# MAME-Controller.net
KiCad netlist of a schematic drawn in EAGLE
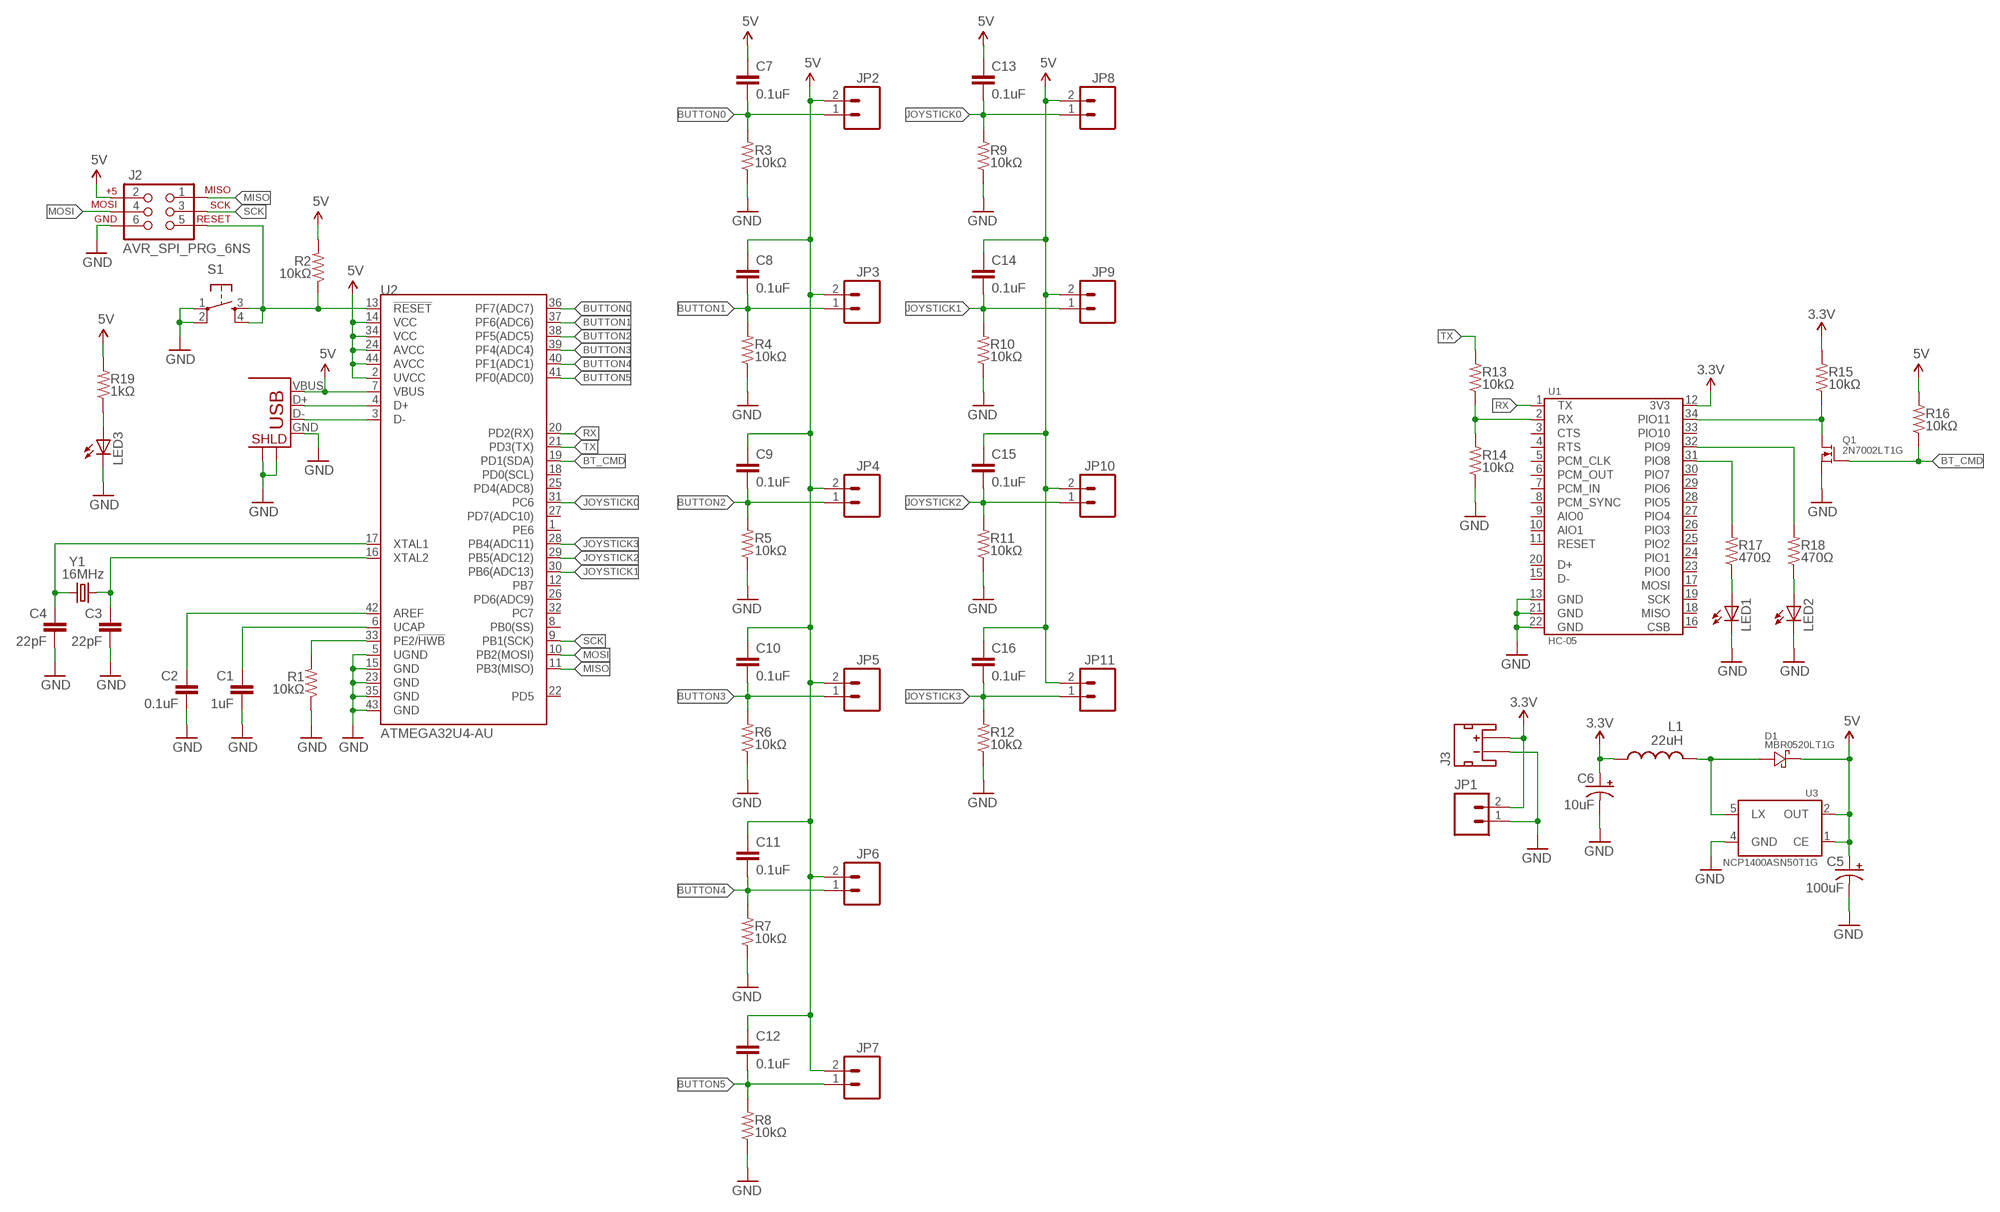
[diagram p0: schematic, sheet 1]

(export (version "E")
  (design (tool "Eeschema 10.0.6"))
  (components
    (comp (ref "C1")
      (value "1uF")
      (footprint "eagle-import:0805")
      (libsource (lib "eagle-import") (part "CAP0805"))
    )
    (comp (ref "C2")
      (value "0.1uF")
      (footprint "eagle-import:0805")
      (libsource (lib "eagle-import") (part "CAP0805"))
    )
    (comp (ref "C3")
      (value "22pF")
      (footprint "eagle-import:0805")
      (libsource (lib "eagle-import") (part "CAP0805"))
    )
    (comp (ref "C4")
      (value "22pF")
      (footprint "eagle-import:0805")
      (libsource (lib "eagle-import") (part "CAP0805"))
    )
    (comp (ref "C5")
      (value "100uF")
      (footprint "eagle-import:CAP_POL-0.35X0.5")
      (libsource (lib "eagle-import") (part "CAP_POL-0.35X0.5"))
    )
    (comp (ref "C6")
      (value "10uF")
      (footprint "eagle-import:EIA3216-KIT")
      (libsource (lib "eagle-import") (part "CAP_POL1206-KIT"))
    )
    (comp (ref "C7")
      (value "0.1uF")
      (footprint "eagle-import:0805")
      (libsource (lib "eagle-import") (part "CAP0805"))
    )
    (comp (ref "C8")
      (value "0.1uF")
      (footprint "eagle-import:0805")
      (libsource (lib "eagle-import") (part "CAP0805"))
    )
    (comp (ref "C9")
      (value "0.1uF")
      (footprint "eagle-import:0805")
      (libsource (lib "eagle-import") (part "CAP0805"))
    )
    (comp (ref "C10")
      (value "0.1uF")
      (footprint "eagle-import:0805")
      (libsource (lib "eagle-import") (part "CAP0805"))
    )
    (comp (ref "C11")
      (value "0.1uF")
      (footprint "eagle-import:0805")
      (libsource (lib "eagle-import") (part "CAP0805"))
    )
    (comp (ref "C12")
      (value "0.1uF")
      (footprint "eagle-import:0805")
      (libsource (lib "eagle-import") (part "CAP0805"))
    )
    (comp (ref "C13")
      (value "0.1uF")
      (footprint "eagle-import:0805")
      (libsource (lib "eagle-import") (part "CAP0805"))
    )
    (comp (ref "C14")
      (value "0.1uF")
      (footprint "eagle-import:0805")
      (libsource (lib "eagle-import") (part "CAP0805"))
    )
    (comp (ref "C15")
      (value "0.1uF")
      (footprint "eagle-import:0805")
      (libsource (lib "eagle-import") (part "CAP0805"))
    )
    (comp (ref "C16")
      (value "0.1uF")
      (footprint "eagle-import:0805")
      (libsource (lib "eagle-import") (part "CAP0805"))
    )
    (comp (ref "D1")
      (value "MBR0520LT1G")
      (footprint "eagle-import:SOD123")
      (libsource (lib "eagle-import") (part "MBR0520LT1G"))
    )
    (comp (ref "J1")
      (value "USB+SHIELD")
      (footprint "eagle-import:USB-B-PTH")
      (libsource (lib "eagle-import") (part "USB+SHIELD"))
    )
    (comp (ref "J2")
      (value "AVR_SPI_PRG_6NS")
      (footprint "eagle-import:2X3-NS")
      (libsource (lib "eagle-import") (part "AVR_SPI_PRG_6NS"))
    )
    (comp (ref "J3")
      (value "JST_2MM_MALE")
      (footprint "eagle-import:JST-2-SMD")
      (libsource (lib "eagle-import") (part "JST_2MM_MALE"))
    )
    (comp (ref "JP1")
      (value "M02PTH")
      (footprint "eagle-import:1X02")
      (libsource (lib "eagle-import") (part "M02PTH"))
    )
    (comp (ref "JP2")
      (value "M02POLAR")
      (footprint "eagle-import:MOLEX-1X2")
      (libsource (lib "eagle-import") (part "M02POLAR"))
    )
    (comp (ref "JP3")
      (value "M02POLAR")
      (footprint "eagle-import:MOLEX-1X2")
      (libsource (lib "eagle-import") (part "M02POLAR"))
    )
    (comp (ref "JP4")
      (value "M02POLAR")
      (footprint "eagle-import:MOLEX-1X2")
      (libsource (lib "eagle-import") (part "M02POLAR"))
    )
    (comp (ref "JP5")
      (value "M02POLAR")
      (footprint "eagle-import:MOLEX-1X2")
      (libsource (lib "eagle-import") (part "M02POLAR"))
    )
    (comp (ref "JP6")
      (value "M02POLAR")
      (footprint "eagle-import:MOLEX-1X2")
      (libsource (lib "eagle-import") (part "M02POLAR"))
    )
    (comp (ref "JP7")
      (value "M02POLAR")
      (footprint "eagle-import:MOLEX-1X2")
      (libsource (lib "eagle-import") (part "M02POLAR"))
    )
    (comp (ref "JP8")
      (value "M02POLAR")
      (footprint "eagle-import:MOLEX-1X2")
      (libsource (lib "eagle-import") (part "M02POLAR"))
    )
    (comp (ref "JP9")
      (value "M02POLAR")
      (footprint "eagle-import:MOLEX-1X2")
      (libsource (lib "eagle-import") (part "M02POLAR"))
    )
    (comp (ref "JP10")
      (value "M02POLAR")
      (footprint "eagle-import:MOLEX-1X2")
      (libsource (lib "eagle-import") (part "M02POLAR"))
    )
    (comp (ref "JP11")
      (value "M02POLAR")
      (footprint "eagle-import:MOLEX-1X2")
      (libsource (lib "eagle-import") (part "M02POLAR"))
    )
    (comp (ref "L1")
      (value "22uH")
      (footprint "eagle-import:0805")
      (libsource (lib "eagle-import") (part "INDUCTOR0805"))
    )
    (comp (ref "LED1")
      (value "LED-FKIT-1206")
      (footprint "eagle-import:FKIT-LED-1206")
      (libsource (lib "eagle-import") (part "LED-FKIT-1206"))
    )
    (comp (ref "LED2")
      (value "LED-FKIT-1206")
      (footprint "eagle-import:FKIT-LED-1206")
      (libsource (lib "eagle-import") (part "LED-FKIT-1206"))
    )
    (comp (ref "LED3")
      (value "LED-FKIT-1206")
      (footprint "eagle-import:FKIT-LED-1206")
      (libsource (lib "eagle-import") (part "LED-FKIT-1206"))
    )
    (comp (ref "Q1")
      (value "2N7002LT1G")
      (footprint "eagle-import:SOT23")
      (libsource (lib "eagle-import") (part "2N7002LT1G"))
    )
    (comp (ref "R1")
      (value "10kΩ")
      (footprint "eagle-import:0805")
      (libsource (lib "eagle-import") (part "RESISTOR0805-RES"))
    )
    (comp (ref "R2")
      (value "10kΩ")
      (footprint "eagle-import:0805")
      (libsource (lib "eagle-import") (part "RESISTOR0805-RES"))
    )
    (comp (ref "R3")
      (value "10kΩ")
      (footprint "eagle-import:0805")
      (libsource (lib "eagle-import") (part "RESISTOR0805-RES"))
    )
    (comp (ref "R4")
      (value "10kΩ")
      (footprint "eagle-import:0805")
      (libsource (lib "eagle-import") (part "RESISTOR0805-RES"))
    )
    (comp (ref "R5")
      (value "10kΩ")
      (footprint "eagle-import:0805")
      (libsource (lib "eagle-import") (part "RESISTOR0805-RES"))
    )
    (comp (ref "R6")
      (value "10kΩ")
      (footprint "eagle-import:0805")
      (libsource (lib "eagle-import") (part "RESISTOR0805-RES"))
    )
    (comp (ref "R7")
      (value "10kΩ")
      (footprint "eagle-import:0805")
      (libsource (lib "eagle-import") (part "RESISTOR0805-RES"))
    )
    (comp (ref "R8")
      (value "10kΩ")
      (footprint "eagle-import:0805")
      (libsource (lib "eagle-import") (part "RESISTOR0805-RES"))
    )
    (comp (ref "R9")
      (value "10kΩ")
      (footprint "eagle-import:0805")
      (libsource (lib "eagle-import") (part "RESISTOR0805-RES"))
    )
    (comp (ref "R10")
      (value "10kΩ")
      (footprint "eagle-import:0805")
      (libsource (lib "eagle-import") (part "RESISTOR0805-RES"))
    )
    (comp (ref "R11")
      (value "10kΩ")
      (footprint "eagle-import:0805")
      (libsource (lib "eagle-import") (part "RESISTOR0805-RES"))
    )
    (comp (ref "R12")
      (value "10kΩ")
      (footprint "eagle-import:0805")
      (libsource (lib "eagle-import") (part "RESISTOR0805-RES"))
    )
    (comp (ref "R13")
      (value "10kΩ")
      (footprint "eagle-import:0805")
      (libsource (lib "eagle-import") (part "RESISTOR0805-RES"))
    )
    (comp (ref "R14")
      (value "10kΩ")
      (footprint "eagle-import:0805")
      (libsource (lib "eagle-import") (part "RESISTOR0805-RES"))
    )
    (comp (ref "R15")
      (value "10kΩ")
      (footprint "eagle-import:0805")
      (libsource (lib "eagle-import") (part "RESISTOR0805-RES"))
    )
    (comp (ref "R16")
      (value "10kΩ")
      (footprint "eagle-import:0805")
      (libsource (lib "eagle-import") (part "RESISTOR0805-RES"))
    )
    (comp (ref "R17")
      (value "470Ω")
      (footprint "eagle-import:0805")
      (libsource (lib "eagle-import") (part "RESISTOR0805-RES"))
    )
    (comp (ref "R18")
      (value "470Ω")
      (footprint "eagle-import:0805")
      (libsource (lib "eagle-import") (part "RESISTOR0805-RES"))
    )
    (comp (ref "R19")
      (value "1kΩ")
      (footprint "eagle-import:0805")
      (libsource (lib "eagle-import") (part "RESISTOR0805-RES"))
    )
    (comp (ref "S1")
      (value "TAC_SWITCHSMD")
      (footprint "eagle-import:TACTILE_SWITCH_SMD")
      (libsource (lib "eagle-import") (part "TAC_SWITCHSMD"))
    )
    (comp (ref "U1")
      (value "HC-05")
      (footprint "eagle-import:HC-05")
      (libsource (lib "eagle-import") (part "HC-05"))
    )
    (comp (ref "U2")
      (value "ATMEGA32U4-AU")
      (footprint "eagle-import:TQFP-44")
      (libsource (lib "eagle-import") (part "ATMEGA32U4-AU"))
    )
    (comp (ref "U3")
      (value "NCP1400ASN50T1G")
      (footprint "eagle-import:SOT23-5")
      (libsource (lib "eagle-import") (part "NCP1400ASN50T1G"))
    )
    (comp (ref "Y1")
      (value "16MHz")
      (footprint "eagle-import:HC49US")
      (libsource (lib "eagle-import") (part "CRYSTALHC49US"))
    )
  )
  (nets
    (net (code "1") (name "3.3V") (class "Default")
      (node (ref "C6") (pin "A") (pinfunction "+_A") (pintype "passive"))
      (node (ref "J3") (pin "2") (pinfunction "+_2") (pintype "bidirectional"))
      (node (ref "JP1") (pin "2") (pinfunction "2_2") (pintype "passive"))
      (node (ref "L1") (pin "2") (pinfunction "2_2") (pintype "passive"))
      (node (ref "R15") (pin "2") (pinfunction "2_2") (pintype "passive"))
      (node (ref "U1") (pin "12") (pinfunction "3V3_12") (pintype "bidirectional"))
    )
    (net (code "2") (name "5V") (class "Default")
      (node (ref "C10") (pin "1") (pinfunction "1_1") (pintype "passive"))
      (node (ref "C11") (pin "1") (pinfunction "1_1") (pintype "passive"))
      (node (ref "C12") (pin "1") (pinfunction "1_1") (pintype "passive"))
      (node (ref "C13") (pin "1") (pinfunction "1_1") (pintype "passive"))
      (node (ref "C14") (pin "1") (pinfunction "1_1") (pintype "passive"))
      (node (ref "C15") (pin "1") (pinfunction "1_1") (pintype "passive"))
      (node (ref "C16") (pin "1") (pinfunction "1_1") (pintype "passive"))
      (node (ref "C5") (pin "+") (pinfunction "+_+") (pintype "passive"))
      (node (ref "C7") (pin "1") (pinfunction "1_1") (pintype "passive"))
      (node (ref "C8") (pin "1") (pinfunction "1_1") (pintype "passive"))
      (node (ref "C9") (pin "1") (pinfunction "1_1") (pintype "passive"))
      (node (ref "D1") (pin "CATHODE") (pinfunction "C_CATHODE") (pintype "bidirectional"))
      (node (ref "J1") (pin "VBUS") (pinfunction "VBUS_VBUS") (pintype "bidirectional"))
      (node (ref "J2") (pin "2") (pinfunction "2_2") (pintype "passive"))
      (node (ref "JP10") (pin "2") (pinfunction "2_2") (pintype "passive"))
      (node (ref "JP11") (pin "2") (pinfunction "2_2") (pintype "passive"))
      (node (ref "JP2") (pin "2") (pinfunction "2_2") (pintype "passive"))
      (node (ref "JP3") (pin "2") (pinfunction "2_2") (pintype "passive"))
      (node (ref "JP4") (pin "2") (pinfunction "2_2") (pintype "passive"))
      (node (ref "JP5") (pin "2") (pinfunction "2_2") (pintype "passive"))
      (node (ref "JP6") (pin "2") (pinfunction "2_2") (pintype "passive"))
      (node (ref "JP7") (pin "2") (pinfunction "2_2") (pintype "passive"))
      (node (ref "JP8") (pin "2") (pinfunction "2_2") (pintype "passive"))
      (node (ref "JP9") (pin "2") (pinfunction "2_2") (pintype "passive"))
      (node (ref "R16") (pin "2") (pinfunction "2_2") (pintype "passive"))
      (node (ref "R19") (pin "2") (pinfunction "2_2") (pintype "passive"))
      (node (ref "R2") (pin "2") (pinfunction "2_2") (pintype "passive"))
      (node (ref "U2") (pin "14") (pinfunction "VCC_14") (pintype "bidirectional"))
      (node (ref "U2") (pin "2") (pinfunction "UVCC_2") (pintype "bidirectional"))
      (node (ref "U2") (pin "24") (pinfunction "AVCC_24") (pintype "bidirectional"))
      (node (ref "U2") (pin "34") (pinfunction "VCC_34") (pintype "bidirectional"))
      (node (ref "U2") (pin "44") (pinfunction "AVCC_44") (pintype "bidirectional"))
      (node (ref "U2") (pin "7") (pinfunction "VBUS_7") (pintype "bidirectional"))
      (node (ref "U3") (pin "1") (pinfunction "CE_1") (pintype "bidirectional"))
      (node (ref "U3") (pin "2") (pinfunction "OUT_2") (pintype "bidirectional"))
    )
    (net (code "3") (name "BT_CMD") (class "Default")
      (node (ref "Q1") (pin "1") (pinfunction "GATE_1") (pintype "bidirectional"))
      (node (ref "R16") (pin "1") (pinfunction "1_1") (pintype "passive"))
      (node (ref "U2") (pin "19") (pinfunction "PD1(SDA)_19") (pintype "bidirectional"))
    )
    (net (code "4") (name "BUTTON0") (class "Default")
      (node (ref "C7") (pin "2") (pinfunction "2_2") (pintype "passive"))
      (node (ref "JP2") (pin "1") (pinfunction "1_1") (pintype "passive"))
      (node (ref "R3") (pin "2") (pinfunction "2_2") (pintype "passive"))
      (node (ref "U2") (pin "36") (pinfunction "PF7(ADC7)_36") (pintype "bidirectional"))
    )
    (net (code "5") (name "BUTTON1") (class "Default")
      (node (ref "C8") (pin "2") (pinfunction "2_2") (pintype "passive"))
      (node (ref "JP3") (pin "1") (pinfunction "1_1") (pintype "passive"))
      (node (ref "R4") (pin "2") (pinfunction "2_2") (pintype "passive"))
      (node (ref "U2") (pin "37") (pinfunction "PF6(ADC6)_37") (pintype "bidirectional"))
    )
    (net (code "6") (name "BUTTON2") (class "Default")
      (node (ref "C9") (pin "2") (pinfunction "2_2") (pintype "passive"))
      (node (ref "JP4") (pin "1") (pinfunction "1_1") (pintype "passive"))
      (node (ref "R5") (pin "2") (pinfunction "2_2") (pintype "passive"))
      (node (ref "U2") (pin "38") (pinfunction "PF5(ADC5)_38") (pintype "bidirectional"))
    )
    (net (code "7") (name "BUTTON3") (class "Default")
      (node (ref "C10") (pin "2") (pinfunction "2_2") (pintype "passive"))
      (node (ref "JP5") (pin "1") (pinfunction "1_1") (pintype "passive"))
      (node (ref "R6") (pin "2") (pinfunction "2_2") (pintype "passive"))
      (node (ref "U2") (pin "39") (pinfunction "PF4(ADC4)_39") (pintype "bidirectional"))
    )
    (net (code "8") (name "BUTTON4") (class "Default")
      (node (ref "C11") (pin "2") (pinfunction "2_2") (pintype "passive"))
      (node (ref "JP6") (pin "1") (pinfunction "1_1") (pintype "passive"))
      (node (ref "R7") (pin "2") (pinfunction "2_2") (pintype "passive"))
      (node (ref "U2") (pin "40") (pinfunction "PF1(ADC1)_40") (pintype "bidirectional"))
    )
    (net (code "9") (name "BUTTON5") (class "Default")
      (node (ref "C12") (pin "2") (pinfunction "2_2") (pintype "passive"))
      (node (ref "JP7") (pin "1") (pinfunction "1_1") (pintype "passive"))
      (node (ref "R8") (pin "2") (pinfunction "2_2") (pintype "passive"))
      (node (ref "U2") (pin "41") (pinfunction "PF0(ADC0)_41") (pintype "bidirectional"))
    )
    (net (code "10") (name "GND") (class "Default")
      (node (ref "C1") (pin "2") (pinfunction "2_2") (pintype "passive"))
      (node (ref "C2") (pin "2") (pinfunction "2_2") (pintype "passive"))
      (node (ref "C3") (pin "2") (pinfunction "2_2") (pintype "passive"))
      (node (ref "C4") (pin "2") (pinfunction "2_2") (pintype "passive"))
      (node (ref "C5") (pin "-") (pinfunction "-_-") (pintype "passive"))
      (node (ref "C6") (pin "C") (pinfunction "-_C") (pintype "passive"))
      (node (ref "J1") (pin "GND") (pinfunction "GND_GND") (pintype "bidirectional"))
      (node (ref "J1") (pin "S1") (pinfunction "P$1_S1") (pintype "bidirectional"))
      (node (ref "J1") (pin "S2") (pinfunction "P$2_S2") (pintype "bidirectional"))
      (node (ref "J2") (pin "6") (pinfunction "6_6") (pintype "passive"))
      (node (ref "J3") (pin "1") (pinfunction "-_1") (pintype "bidirectional"))
      (node (ref "JP1") (pin "1") (pinfunction "1_1") (pintype "passive"))
      (node (ref "LED1") (pin "C") (pinfunction "C_C") (pintype "passive"))
      (node (ref "LED2") (pin "C") (pinfunction "C_C") (pintype "passive"))
      (node (ref "LED3") (pin "C") (pinfunction "C_C") (pintype "passive"))
      (node (ref "Q1") (pin "2") (pinfunction "SOURCE_2") (pintype "bidirectional"))
      (node (ref "R1") (pin "1") (pinfunction "1_1") (pintype "passive"))
      (node (ref "R10") (pin "1") (pinfunction "1_1") (pintype "passive"))
      (node (ref "R11") (pin "1") (pinfunction "1_1") (pintype "passive"))
      (node (ref "R12") (pin "1") (pinfunction "1_1") (pintype "passive"))
      (node (ref "R14") (pin "1") (pinfunction "1_1") (pintype "passive"))
      (node (ref "R3") (pin "1") (pinfunction "1_1") (pintype "passive"))
      (node (ref "R4") (pin "1") (pinfunction "1_1") (pintype "passive"))
      (node (ref "R5") (pin "1") (pinfunction "1_1") (pintype "passive"))
      (node (ref "R6") (pin "1") (pinfunction "1_1") (pintype "passive"))
      (node (ref "R7") (pin "1") (pinfunction "1_1") (pintype "passive"))
      (node (ref "R8") (pin "1") (pinfunction "1_1") (pintype "passive"))
      (node (ref "R9") (pin "1") (pinfunction "1_1") (pintype "passive"))
      (node (ref "S1") (pin "1") (pinfunction "1_1") (pintype "passive"))
      (node (ref "S1") (pin "2") (pinfunction "2_2") (pintype "passive"))
      (node (ref "U1") (pin "13") (pinfunction "GND_13") (pintype "bidirectional"))
      (node (ref "U1") (pin "21") (pinfunction "GND_21") (pintype "bidirectional"))
      (node (ref "U1") (pin "22") (pinfunction "GND_22") (pintype "bidirectional"))
      (node (ref "U2") (pin "15") (pinfunction "GND_15") (pintype "bidirectional"))
      (node (ref "U2") (pin "23") (pinfunction "GND_23") (pintype "bidirectional"))
      (node (ref "U2") (pin "35") (pinfunction "GND_35") (pintype "bidirectional"))
      (node (ref "U2") (pin "43") (pinfunction "GND_43") (pintype "bidirectional"))
      (node (ref "U2") (pin "5") (pinfunction "UGND_5") (pintype "bidirectional"))
      (node (ref "U3") (pin "4") (pinfunction "GND_4") (pintype "bidirectional"))
    )
    (net (code "11") (name "JOYSTICK0") (class "Default")
      (node (ref "C13") (pin "2") (pinfunction "2_2") (pintype "passive"))
      (node (ref "JP8") (pin "1") (pinfunction "1_1") (pintype "passive"))
      (node (ref "R9") (pin "2") (pinfunction "2_2") (pintype "passive"))
      (node (ref "U2") (pin "31") (pinfunction "PC6_31") (pintype "bidirectional"))
    )
    (net (code "12") (name "JOYSTICK1") (class "Default")
      (node (ref "C14") (pin "2") (pinfunction "2_2") (pintype "passive"))
      (node (ref "JP9") (pin "1") (pinfunction "1_1") (pintype "passive"))
      (node (ref "R10") (pin "2") (pinfunction "2_2") (pintype "passive"))
      (node (ref "U2") (pin "30") (pinfunction "PB6(ADC13)_30") (pintype "bidirectional"))
    )
    (net (code "13") (name "JOYSTICK2") (class "Default")
      (node (ref "C15") (pin "2") (pinfunction "2_2") (pintype "passive"))
      (node (ref "JP10") (pin "1") (pinfunction "1_1") (pintype "passive"))
      (node (ref "R11") (pin "2") (pinfunction "2_2") (pintype "passive"))
      (node (ref "U2") (pin "29") (pinfunction "PB5(ADC12)_29") (pintype "bidirectional"))
    )
    (net (code "14") (name "JOYSTICK3") (class "Default")
      (node (ref "C16") (pin "2") (pinfunction "2_2") (pintype "passive"))
      (node (ref "JP11") (pin "1") (pinfunction "1_1") (pintype "passive"))
      (node (ref "R12") (pin "2") (pinfunction "2_2") (pintype "passive"))
      (node (ref "U2") (pin "28") (pinfunction "PB4(ADC11)_28") (pintype "bidirectional"))
    )
    (net (code "15") (name "MISO") (class "Default")
      (node (ref "J2") (pin "1") (pinfunction "1_1") (pintype "passive"))
      (node (ref "U2") (pin "11") (pinfunction "PB3(MISO)_11") (pintype "bidirectional"))
    )
    (net (code "16") (name "MOSI") (class "Default")
      (node (ref "J2") (pin "4") (pinfunction "4_4") (pintype "passive"))
      (node (ref "U2") (pin "10") (pinfunction "PB2(MOSI)_10") (pintype "bidirectional"))
    )
    (net (code "17") (name "Net-(D1-A)") (class "Default")
      (node (ref "D1") (pin "ANODE") (pinfunction "A_ANODE") (pintype "bidirectional"))
      (node (ref "L1") (pin "1") (pinfunction "1_1") (pintype "passive"))
      (node (ref "U3") (pin "5") (pinfunction "LX_5") (pintype "bidirectional"))
    )
    (net (code "18") (name "Net-(LED1-PadA)") (class "Default")
      (node (ref "LED1") (pin "A") (pinfunction "A_A") (pintype "passive"))
      (node (ref "R17") (pin "1") (pinfunction "1_1") (pintype "passive"))
    )
    (net (code "19") (name "Net-(LED2-PadA)") (class "Default")
      (node (ref "LED2") (pin "A") (pinfunction "A_A") (pintype "passive"))
      (node (ref "R18") (pin "1") (pinfunction "1_1") (pintype "passive"))
    )
    (net (code "20") (name "Net-(LED3-PadA)") (class "Default")
      (node (ref "LED3") (pin "A") (pinfunction "A_A") (pintype "passive"))
      (node (ref "R19") (pin "1") (pinfunction "1_1") (pintype "passive"))
    )
    (net (code "21") (name "Net-(Q1-DRAIN)") (class "Default")
      (node (ref "Q1") (pin "3") (pinfunction "DRAIN_3") (pintype "bidirectional"))
      (node (ref "R15") (pin "1") (pinfunction "1_1") (pintype "passive"))
      (node (ref "U1") (pin "34") (pinfunction "PIO11_34") (pintype "bidirectional"))
    )
    (net (code "22") (name "Net-(U1-PIO8)") (class "Default")
      (node (ref "R17") (pin "2") (pinfunction "2_2") (pintype "passive"))
      (node (ref "U1") (pin "31") (pinfunction "PIO8_31") (pintype "bidirectional"))
    )
    (net (code "23") (name "Net-(U1-PIO9)") (class "Default")
      (node (ref "R18") (pin "2") (pinfunction "2_2") (pintype "passive"))
      (node (ref "U1") (pin "32") (pinfunction "PIO9_32") (pintype "bidirectional"))
    )
    (net (code "24") (name "Net-(U1-RX)") (class "Default")
      (node (ref "R13") (pin "1") (pinfunction "1_1") (pintype "passive"))
      (node (ref "R14") (pin "2") (pinfunction "2_2") (pintype "passive"))
      (node (ref "U1") (pin "2") (pinfunction "RX_2") (pintype "bidirectional"))
    )
    (net (code "25") (name "Net-(U2-AREF)") (class "Default")
      (node (ref "C2") (pin "1") (pinfunction "1_1") (pintype "passive"))
      (node (ref "U2") (pin "42") (pinfunction "AREF_42") (pintype "bidirectional"))
    )
    (net (code "26") (name "Net-(U2-D+)") (class "Default")
      (node (ref "J1") (pin "D+") (pinfunction "D+_D+") (pintype "bidirectional"))
      (node (ref "U2") (pin "4") (pinfunction "D+_4") (pintype "bidirectional"))
    )
    (net (code "27") (name "Net-(U2-D-)") (class "Default")
      (node (ref "J1") (pin "D-") (pinfunction "D-_D-") (pintype "bidirectional"))
      (node (ref "U2") (pin "3") (pinfunction "D-_3") (pintype "bidirectional"))
    )
    (net (code "28") (name "Net-(U2-PE2{slash}~{HWB})") (class "Default")
      (node (ref "R1") (pin "2") (pinfunction "2_2") (pintype "passive"))
      (node (ref "U2") (pin "33") (pinfunction "PE2/~{HWB}_33") (pintype "bidirectional"))
    )
    (net (code "29") (name "Net-(U2-UCAP)") (class "Default")
      (node (ref "C1") (pin "1") (pinfunction "1_1") (pintype "passive"))
      (node (ref "U2") (pin "6") (pinfunction "UCAP_6") (pintype "bidirectional"))
    )
    (net (code "30") (name "Net-(U2-XTAL1)") (class "Default")
      (node (ref "C4") (pin "1") (pinfunction "1_1") (pintype "passive"))
      (node (ref "U2") (pin "17") (pinfunction "XTAL1_17") (pintype "bidirectional"))
      (node (ref "Y1") (pin "1") (pinfunction "1_1") (pintype "passive"))
    )
    (net (code "31") (name "Net-(U2-XTAL2)") (class "Default")
      (node (ref "C3") (pin "1") (pinfunction "1_1") (pintype "passive"))
      (node (ref "U2") (pin "16") (pinfunction "XTAL2_16") (pintype "bidirectional"))
      (node (ref "Y1") (pin "2") (pinfunction "2_2") (pintype "passive"))
    )
    (net (code "32") (name "Net-(U2-~{RESET})") (class "Default")
      (node (ref "J2") (pin "5") (pinfunction "5_5") (pintype "passive"))
      (node (ref "R2") (pin "1") (pinfunction "1_1") (pintype "passive"))
      (node (ref "S1") (pin "3") (pinfunction "3_3") (pintype "passive"))
      (node (ref "S1") (pin "4") (pinfunction "4_4") (pintype "passive"))
      (node (ref "U2") (pin "13") (pinfunction "~{RESET}_13") (pintype "bidirectional"))
    )
    (net (code "33") (name "RX") (class "Default")
      (node (ref "U1") (pin "1") (pinfunction "TX_1") (pintype "bidirectional"))
      (node (ref "U2") (pin "20") (pinfunction "PD2(RX)_20") (pintype "bidirectional"))
    )
    (net (code "34") (name "SCK") (class "Default")
      (node (ref "J2") (pin "3") (pinfunction "3_3") (pintype "passive"))
      (node (ref "U2") (pin "9") (pinfunction "PB1(SCK)_9") (pintype "bidirectional"))
    )
    (net (code "35") (name "TX") (class "Default")
      (node (ref "R13") (pin "2") (pinfunction "2_2") (pintype "passive"))
      (node (ref "U2") (pin "21") (pinfunction "PD3(TX)_21") (pintype "bidirectional"))
    )
    (net (code "36") (name "unconnected-(J3-PAD1-PadNC1)") (class "Default")
      (node (ref "J3") (pin "NC1") (pinfunction "PAD1_NC1") (pintype "bidirectional"))
    )
    (net (code "37") (name "unconnected-(J3-PAD2-PadNC2)") (class "Default")
      (node (ref "J3") (pin "NC2") (pinfunction "PAD2_NC2") (pintype "bidirectional"))
    )
    (net (code "38") (name "unconnected-(U1-AIO0-Pad9)") (class "Default")
      (node (ref "U1") (pin "9") (pinfunction "AIO0_9") (pintype "bidirectional"))
    )
    (net (code "39") (name "unconnected-(U1-AIO1-Pad10)") (class "Default")
      (node (ref "U1") (pin "10") (pinfunction "AIO1_10") (pintype "bidirectional"))
    )
    (net (code "40") (name "unconnected-(U1-CSB-Pad16)") (class "Default")
      (node (ref "U1") (pin "16") (pinfunction "CSB_16") (pintype "bidirectional"))
    )
    (net (code "41") (name "unconnected-(U1-CTS-Pad3)") (class "Default")
      (node (ref "U1") (pin "3") (pinfunction "CTS_3") (pintype "bidirectional"))
    )
    (net (code "42") (name "unconnected-(U1-D+-Pad20)") (class "Default")
      (node (ref "U1") (pin "20") (pinfunction "D+_20") (pintype "bidirectional"))
    )
    (net (code "43") (name "unconnected-(U1-D--Pad15)") (class "Default")
      (node (ref "U1") (pin "15") (pinfunction "D-_15") (pintype "bidirectional"))
    )
    (net (code "44") (name "unconnected-(U1-MISO-Pad18)") (class "Default")
      (node (ref "U1") (pin "18") (pinfunction "MISO_18") (pintype "bidirectional"))
    )
    (net (code "45") (name "unconnected-(U1-MOSI-Pad17)") (class "Default")
      (node (ref "U1") (pin "17") (pinfunction "MOSI_17") (pintype "bidirectional"))
    )
    (net (code "46") (name "unconnected-(U1-PCM_CLK-Pad5)") (class "Default")
      (node (ref "U1") (pin "5") (pinfunction "PCM_CLK_5") (pintype "bidirectional"))
    )
    (net (code "47") (name "unconnected-(U1-PCM_IN-Pad7)") (class "Default")
      (node (ref "U1") (pin "7") (pinfunction "PCM_IN_7") (pintype "bidirectional"))
    )
    (net (code "48") (name "unconnected-(U1-PCM_OUT-Pad6)") (class "Default")
      (node (ref "U1") (pin "6") (pinfunction "PCM_OUT_6") (pintype "bidirectional"))
    )
    (net (code "49") (name "unconnected-(U1-PCM_SYNC-Pad8)") (class "Default")
      (node (ref "U1") (pin "8") (pinfunction "PCM_SYNC_8") (pintype "bidirectional"))
    )
    (net (code "50") (name "unconnected-(U1-PIO0-Pad23)") (class "Default")
      (node (ref "U1") (pin "23") (pinfunction "PIO0_23") (pintype "bidirectional"))
    )
    (net (code "51") (name "unconnected-(U1-PIO1-Pad24)") (class "Default")
      (node (ref "U1") (pin "24") (pinfunction "PIO1_24") (pintype "bidirectional"))
    )
    (net (code "52") (name "unconnected-(U1-PIO2-Pad25)") (class "Default")
      (node (ref "U1") (pin "25") (pinfunction "PIO2_25") (pintype "bidirectional"))
    )
    (net (code "53") (name "unconnected-(U1-PIO3-Pad26)") (class "Default")
      (node (ref "U1") (pin "26") (pinfunction "PIO3_26") (pintype "bidirectional"))
    )
    (net (code "54") (name "unconnected-(U1-PIO4-Pad27)") (class "Default")
      (node (ref "U1") (pin "27") (pinfunction "PIO4_27") (pintype "bidirectional"))
    )
    (net (code "55") (name "unconnected-(U1-PIO5-Pad28)") (class "Default")
      (node (ref "U1") (pin "28") (pinfunction "PIO5_28") (pintype "bidirectional"))
    )
    (net (code "56") (name "unconnected-(U1-PIO6-Pad29)") (class "Default")
      (node (ref "U1") (pin "29") (pinfunction "PIO6_29") (pintype "bidirectional"))
    )
    (net (code "57") (name "unconnected-(U1-PIO7-Pad30)") (class "Default")
      (node (ref "U1") (pin "30") (pinfunction "PIO7_30") (pintype "bidirectional"))
    )
    (net (code "58") (name "unconnected-(U1-PIO10-Pad33)") (class "Default")
      (node (ref "U1") (pin "33") (pinfunction "PIO10_33") (pintype "bidirectional"))
    )
    (net (code "59") (name "unconnected-(U1-RESET-Pad11)") (class "Default")
      (node (ref "U1") (pin "11") (pinfunction "RESET_11") (pintype "bidirectional"))
    )
    (net (code "60") (name "unconnected-(U1-RTS-Pad4)") (class "Default")
      (node (ref "U1") (pin "4") (pinfunction "RTS_4") (pintype "bidirectional"))
    )
    (net (code "61") (name "unconnected-(U1-SCK-Pad19)") (class "Default")
      (node (ref "U1") (pin "19") (pinfunction "SCK_19") (pintype "bidirectional"))
    )
    (net (code "62") (name "unconnected-(U2-PB0(SS)-Pad8)") (class "Default")
      (node (ref "U2") (pin "8") (pinfunction "PB0(SS)_8") (pintype "bidirectional"))
    )
    (net (code "63") (name "unconnected-(U2-PB7-Pad12)") (class "Default")
      (node (ref "U2") (pin "12") (pinfunction "PB7_12") (pintype "bidirectional"))
    )
    (net (code "64") (name "unconnected-(U2-PC7-Pad32)") (class "Default")
      (node (ref "U2") (pin "32") (pinfunction "PC7_32") (pintype "bidirectional"))
    )
    (net (code "65") (name "unconnected-(U2-PD0(SCL)-Pad18)") (class "Default")
      (node (ref "U2") (pin "18") (pinfunction "PD0(SCL)_18") (pintype "bidirectional"))
    )
    (net (code "66") (name "unconnected-(U2-PD4(ADC8)-Pad25)") (class "Default")
      (node (ref "U2") (pin "25") (pinfunction "PD4(ADC8)_25") (pintype "bidirectional"))
    )
    (net (code "67") (name "unconnected-(U2-PD5-Pad22)") (class "Default")
      (node (ref "U2") (pin "22") (pinfunction "PD5_22") (pintype "bidirectional"))
    )
    (net (code "68") (name "unconnected-(U2-PD6(ADC9)-Pad26)") (class "Default")
      (node (ref "U2") (pin "26") (pinfunction "PD6(ADC9)_26") (pintype "bidirectional"))
    )
    (net (code "69") (name "unconnected-(U2-PD7(ADC10)-Pad27)") (class "Default")
      (node (ref "U2") (pin "27") (pinfunction "PD7(ADC10)_27") (pintype "bidirectional"))
    )
    (net (code "70") (name "unconnected-(U2-PE6-Pad1)") (class "Default")
      (node (ref "U2") (pin "1") (pinfunction "PE6_1") (pintype "bidirectional"))
    )
  )
)
